# Top.net
KiCad netlist of a schematic drawn in EAGLE
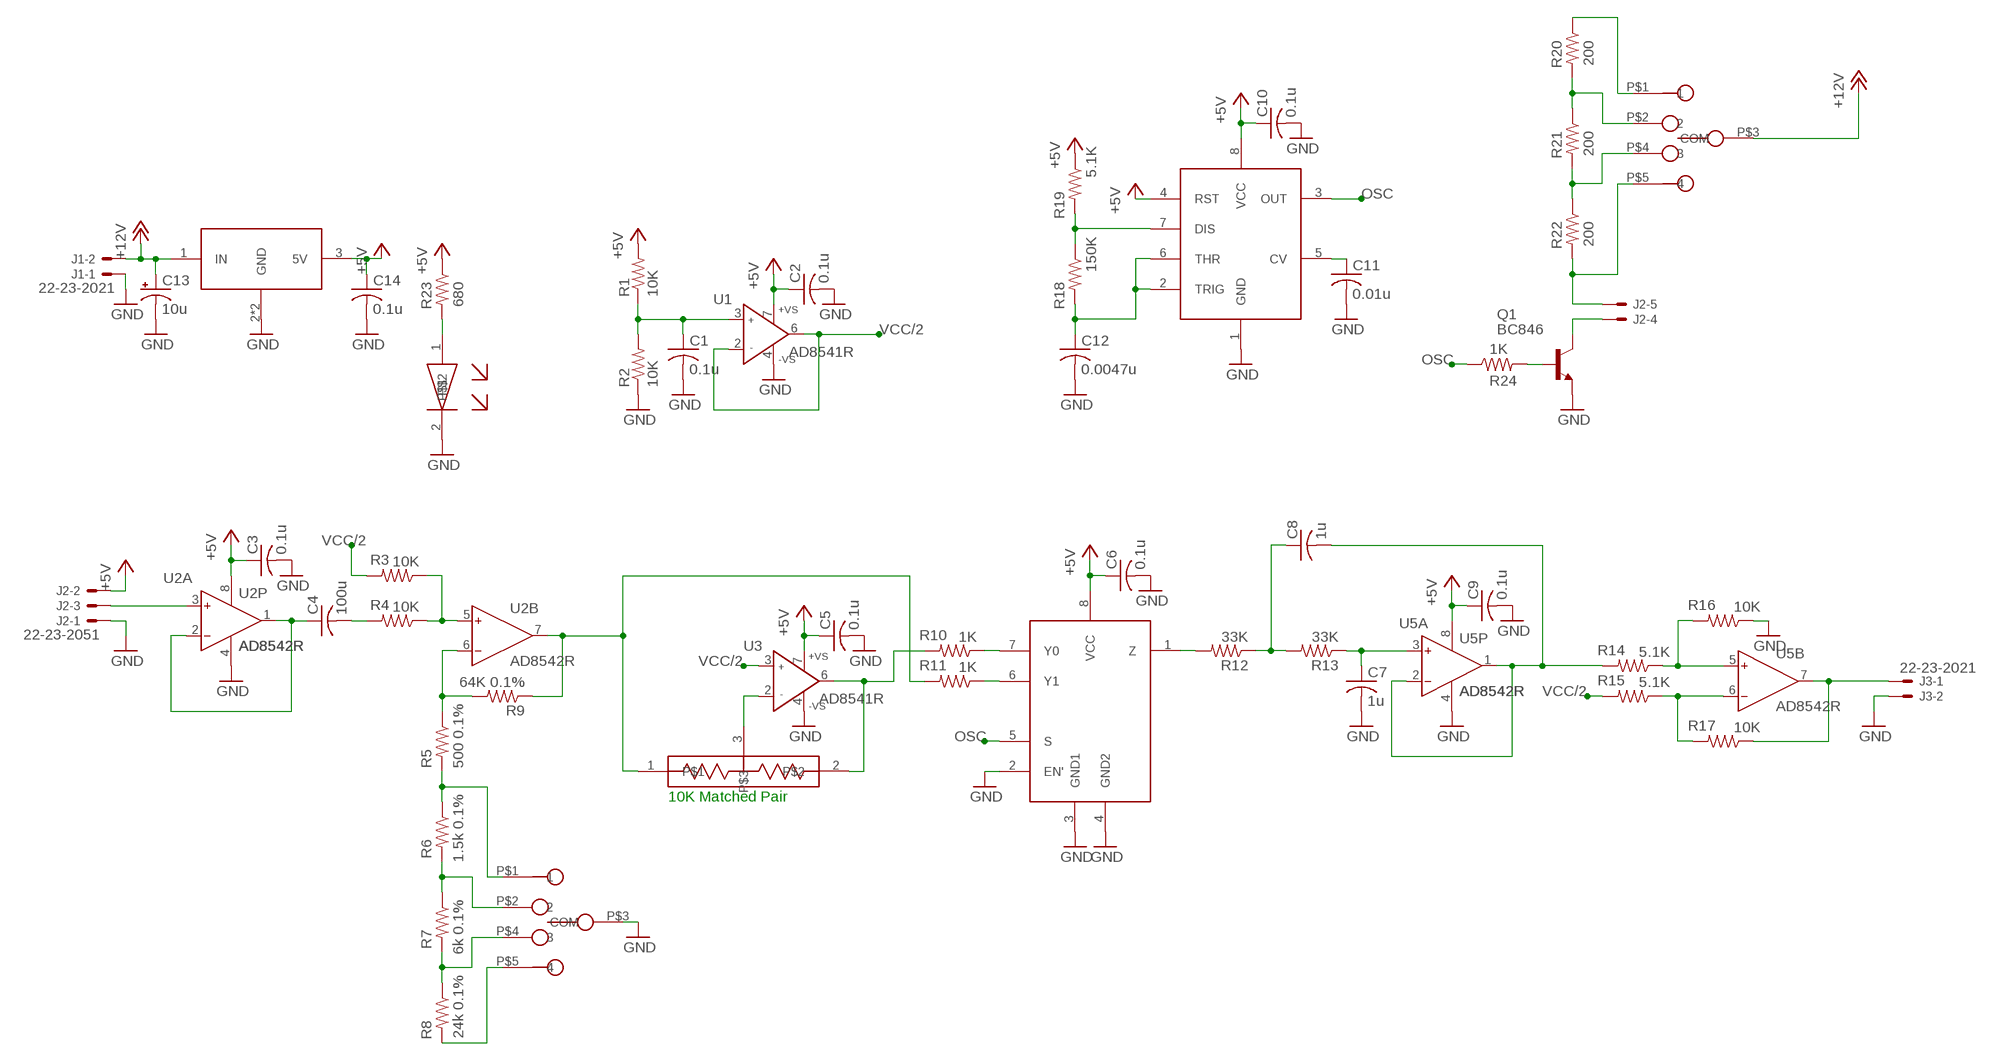
[diagram p0: schematic, sheet 1]

(export (version "E")
  (design (tool "Eeschema 10.0.6"))
  (components
    (comp (ref "C1")
      (value "0.1u")
      (footprint "eagle-import:C0805")
      (libsource (lib "eagle-import") (part "C-USC0805"))
    )
    (comp (ref "C2")
      (value "0.1u")
      (footprint "eagle-import:C0805")
      (libsource (lib "eagle-import") (part "C-USC0805"))
    )
    (comp (ref "C3")
      (value "0.1u")
      (footprint "eagle-import:C0805")
      (libsource (lib "eagle-import") (part "C-USC0805"))
    )
    (comp (ref "C4")
      (value "100u")
      (footprint "eagle-import:C1206")
      (libsource (lib "eagle-import") (part "C-USC1206"))
    )
    (comp (ref "C5")
      (value "0.1u")
      (footprint "eagle-import:C0805")
      (libsource (lib "eagle-import") (part "C-USC0805"))
    )
    (comp (ref "C6")
      (value "0.1u")
      (footprint "eagle-import:C0805")
      (libsource (lib "eagle-import") (part "C-USC0805"))
    )
    (comp (ref "C7")
      (value "1u")
      (footprint "eagle-import:C0805")
      (libsource (lib "eagle-import") (part "C-USC0805"))
    )
    (comp (ref "C8")
      (value "1u")
      (footprint "eagle-import:C0805")
      (libsource (lib "eagle-import") (part "C-USC0805"))
    )
    (comp (ref "C9")
      (value "0.1u")
      (footprint "eagle-import:C0805")
      (libsource (lib "eagle-import") (part "C-USC0805"))
    )
    (comp (ref "C10")
      (value "0.1u")
      (footprint "eagle-import:C0805")
      (libsource (lib "eagle-import") (part "C-USC0805"))
    )
    (comp (ref "C11")
      (value "0.01u")
      (footprint "eagle-import:C0805")
      (libsource (lib "eagle-import") (part "C-USC0805"))
    )
    (comp (ref "C12")
      (value "0.0047u")
      (footprint "eagle-import:C0805")
      (libsource (lib "eagle-import") (part "C-USC0805"))
    )
    (comp (ref "C13")
      (value "10u")
      (footprint "eagle-import:E2-5")
      (libsource (lib "eagle-import") (part "CPOL-USE2-5"))
    )
    (comp (ref "C14")
      (value "0.1u")
      (footprint "eagle-import:C0805")
      (libsource (lib "eagle-import") (part "C-USC0805"))
    )
    (comp (ref "D1")
      (value "LGN971")
      (footprint "eagle-import:R1206")
      (libsource (lib "eagle-import") (part "LGN971"))
    )
    (comp (ref "J1")
      (value "22-23-2021")
      (footprint "eagle-import:22-23-2021")
      (fields (field (name "MF") "MOLEX"))
      (libsource (lib "eagle-import") (part "22-23-2021"))
    )
    (comp (ref "J2")
      (value "22-23-2051")
      (footprint "eagle-import:22-23-2051")
      (fields (field (name "MF") "MOLEX"))
      (libsource (lib "eagle-import") (part "22-23-2051"))
    )
    (comp (ref "J3")
      (value "22-23-2021")
      (footprint "eagle-import:22-23-2021")
      (fields (field (name "MF") "MOLEX"))
      (libsource (lib "eagle-import") (part "22-23-2021"))
    )
    (comp (ref "Q1")
      (value "BC846")
      (footprint "eagle-import:SOT23")
      (libsource (lib "eagle-import") (part "BC846"))
    )
    (comp (ref "R1")
      (value "10K")
      (footprint "eagle-import:R0805")
      (libsource (lib "eagle-import") (part "R-US_R0805"))
    )
    (comp (ref "R2")
      (value "10K")
      (footprint "eagle-import:R0805")
      (libsource (lib "eagle-import") (part "R-US_R0805"))
    )
    (comp (ref "R3")
      (value "10K")
      (footprint "eagle-import:R0805")
      (libsource (lib "eagle-import") (part "R-US_R0805"))
    )
    (comp (ref "R4")
      (value "10K")
      (footprint "eagle-import:R0805")
      (libsource (lib "eagle-import") (part "R-US_R0805"))
    )
    (comp (ref "R5")
      (value "500 0.1%")
      (footprint "eagle-import:R0805")
      (libsource (lib "eagle-import") (part "R-US_R0805"))
    )
    (comp (ref "R6")
      (value "1.5k 0.1%")
      (footprint "eagle-import:R0805")
      (libsource (lib "eagle-import") (part "R-US_R0805"))
    )
    (comp (ref "R7")
      (value "6k 0.1%")
      (footprint "eagle-import:R0805")
      (libsource (lib "eagle-import") (part "R-US_R0805"))
    )
    (comp (ref "R8")
      (value "24k 0.1%")
      (footprint "eagle-import:R0805")
      (libsource (lib "eagle-import") (part "R-US_R0805"))
    )
    (comp (ref "R9")
      (value "64K 0.1%")
      (footprint "eagle-import:R0805")
      (libsource (lib "eagle-import") (part "R-US_R0805"))
    )
    (comp (ref "R10")
      (value "1K")
      (footprint "eagle-import:R0805")
      (libsource (lib "eagle-import") (part "R-US_R0805"))
    )
    (comp (ref "R11")
      (value "1K")
      (footprint "eagle-import:R0805")
      (libsource (lib "eagle-import") (part "R-US_R0805"))
    )
    (comp (ref "R12")
      (value "33K")
      (footprint "eagle-import:R0805")
      (libsource (lib "eagle-import") (part "R-US_R0805"))
    )
    (comp (ref "R13")
      (value "33K")
      (footprint "eagle-import:R0805")
      (libsource (lib "eagle-import") (part "R-US_R0805"))
    )
    (comp (ref "R14")
      (value "5.1K")
      (footprint "eagle-import:R0805")
      (libsource (lib "eagle-import") (part "R-US_R0805"))
    )
    (comp (ref "R15")
      (value "5.1K")
      (footprint "eagle-import:R0805")
      (libsource (lib "eagle-import") (part "R-US_R0805"))
    )
    (comp (ref "R16")
      (value "10K")
      (footprint "eagle-import:R0805")
      (libsource (lib "eagle-import") (part "R-US_R0805"))
    )
    (comp (ref "R17")
      (value "10K")
      (footprint "eagle-import:R0805")
      (libsource (lib "eagle-import") (part "R-US_R0805"))
    )
    (comp (ref "R18")
      (value "150K")
      (footprint "eagle-import:R0805")
      (libsource (lib "eagle-import") (part "R-US_R0805"))
    )
    (comp (ref "R19")
      (value "5.1K")
      (footprint "eagle-import:R0805")
      (libsource (lib "eagle-import") (part "R-US_R0805"))
    )
    (comp (ref "R20")
      (value "200")
      (footprint "eagle-import:R0805")
      (libsource (lib "eagle-import") (part "R-US_R0805"))
    )
    (comp (ref "R21")
      (value "200")
      (footprint "eagle-import:R0805")
      (libsource (lib "eagle-import") (part "R-US_R0805"))
    )
    (comp (ref "R22")
      (value "200")
      (footprint "eagle-import:R0805")
      (libsource (lib "eagle-import") (part "R-US_R0805"))
    )
    (comp (ref "R23")
      (value "680")
      (footprint "eagle-import:R0805")
      (libsource (lib "eagle-import") (part "R-US_R0805"))
    )
    (comp (ref "R24")
      (value "1K")
      (footprint "eagle-import:R0805")
      (libsource (lib "eagle-import") (part "R-US_R0805"))
    )
    (comp (ref "RN1")
      (value "MPMT2002")
      (footprint "eagle-import:SOT23")
      (libsource (lib "eagle-import") (part "MPMT2002"))
    )
    (comp (ref "SW1")
      (value "STS1400")
      (footprint "eagle-import:2-3SW")
      (libsource (lib "eagle-import") (part "STS1400"))
    )
    (comp (ref "SW2")
      (value "STS1400")
      (footprint "eagle-import:2-3SW")
      (libsource (lib "eagle-import") (part "STS1400"))
    )
    (comp (ref "U1")
      (value "AD8541R")
      (footprint "eagle-import:SO8")
      (fields (field (name "MPN") "AD8541ARZ"))
      (libsource (lib "eagle-import") (part "AD8541R"))
    )
    (comp (ref "U2")
      (value "AD8542R")
      (footprint "eagle-import:SO8")
      (fields (field (name "MF") "ALTERA CORPORATION") (field (name "MPN") "AD8542ARZ-REEL"))
      (libsource (lib "eagle-import") (part "AD8542R"))
    )
    (comp (ref "U3")
      (value "AD8541R")
      (footprint "eagle-import:SO8")
      (fields (field (name "MPN") "AD8541ARZ"))
      (libsource (lib "eagle-import") (part "AD8541R"))
    )
    (comp (ref "U4")
      (value "74LVC1G53")
      (footprint "eagle-import:SOP08")
      (libsource (lib "eagle-import") (part "74LVC1G53"))
    )
    (comp (ref "U5")
      (value "AD8542R")
      (footprint "eagle-import:SO8")
      (fields (field (name "MF") "ALTERA CORPORATION") (field (name "MPN") "AD8542ARZ-REEL"))
      (libsource (lib "eagle-import") (part "AD8542R"))
    )
    (comp (ref "U6")
      (value "NA555")
      (footprint "eagle-import:SO8")
      (libsource (lib "eagle-import") (part "NA555"))
    )
    (comp (ref "U7")
      (value "UA78M05CDCYR")
      (footprint "eagle-import:SOT223-W")
      (libsource (lib "eagle-import") (part "UA78M05CDCYR"))
    )
  )
  (nets
    (net (code "1") (name "+5V") (class "Default")
      (node (ref "C10") (pin "1") (pinfunction "1_1") (pintype "passive"))
      (node (ref "C14") (pin "1") (pinfunction "1_1") (pintype "passive"))
      (node (ref "C2") (pin "1") (pinfunction "1_1") (pintype "passive"))
      (node (ref "C3") (pin "1") (pinfunction "1_1") (pintype "passive"))
      (node (ref "C5") (pin "1") (pinfunction "1_1") (pintype "passive"))
      (node (ref "C6") (pin "1") (pinfunction "1_1") (pintype "passive"))
      (node (ref "C9") (pin "1") (pinfunction "1_1") (pintype "passive"))
      (node (ref "J2") (pin "2") (pinfunction "S_2") (pintype "passive"))
      (node (ref "R1") (pin "2") (pinfunction "2_2") (pintype "passive"))
      (node (ref "R19") (pin "1") (pinfunction "1_1") (pintype "passive"))
      (node (ref "R23") (pin "1") (pinfunction "1_1") (pintype "passive"))
      (node (ref "U1") (pin "7") (pinfunction "+VS_7") (pintype "input"))
      (node (ref "U2") (pin "8") (pinfunction "V+_8") (pintype "power_in"))
      (node (ref "U3") (pin "7") (pinfunction "+VS_7") (pintype "input"))
      (node (ref "U4") (pin "8") (pinfunction "VCC_8") (pintype "bidirectional"))
      (node (ref "U5") (pin "8") (pinfunction "V+_8") (pintype "power_in"))
      (node (ref "U6") (pin "4") (pinfunction "RST_4") (pintype "bidirectional"))
      (node (ref "U6") (pin "8") (pinfunction "VCC_8") (pintype "bidirectional"))
      (node (ref "U7") (pin "3") (pinfunction "5V_3") (pintype "bidirectional"))
    )
    (net (code "2") (name "+12V") (class "Default")
      (node (ref "C13") (pin "+") (pinfunction "+_+") (pintype "passive"))
      (node (ref "J1") (pin "2") (pinfunction "S_2") (pintype "passive"))
      (node (ref "SW2") (pin "P$3") (pinfunction "COM_P$3") (pintype "bidirectional"))
      (node (ref "U7") (pin "1") (pinfunction "IN_1") (pintype "bidirectional"))
    )
    (net (code "3") (name "/OSC") (class "Default")
      (node (ref "R24") (pin "1") (pinfunction "1_1") (pintype "passive"))
      (node (ref "U4") (pin "5") (pinfunction "S_5") (pintype "bidirectional"))
      (node (ref "U6") (pin "3") (pinfunction "OUT_3") (pintype "bidirectional"))
    )
    (net (code "4") (name "/VCC{slash}2") (class "Default")
      (node (ref "R15") (pin "2") (pinfunction "2_2") (pintype "passive"))
      (node (ref "R3") (pin "2") (pinfunction "2_2") (pintype "passive"))
      (node (ref "U1") (pin "2") (pinfunction "IN-_2") (pintype "input"))
      (node (ref "U1") (pin "6") (pinfunction "OUT_6") (pintype "output"))
      (node (ref "U3") (pin "3") (pinfunction "IN+_3") (pintype "input"))
    )
    (net (code "5") (name "GND") (class "Default")
      (node (ref "C1") (pin "2") (pinfunction "2_2") (pintype "passive"))
      (node (ref "C10") (pin "2") (pinfunction "2_2") (pintype "passive"))
      (node (ref "C11") (pin "2") (pinfunction "2_2") (pintype "passive"))
      (node (ref "C12") (pin "2") (pinfunction "2_2") (pintype "passive"))
      (node (ref "C13") (pin "-") (pinfunction "-_-") (pintype "passive"))
      (node (ref "C14") (pin "2") (pinfunction "2_2") (pintype "passive"))
      (node (ref "C2") (pin "2") (pinfunction "2_2") (pintype "passive"))
      (node (ref "C3") (pin "2") (pinfunction "2_2") (pintype "passive"))
      (node (ref "C5") (pin "2") (pinfunction "2_2") (pintype "passive"))
      (node (ref "C6") (pin "2") (pinfunction "2_2") (pintype "passive"))
      (node (ref "C7") (pin "2") (pinfunction "2_2") (pintype "passive"))
      (node (ref "C9") (pin "2") (pinfunction "2_2") (pintype "passive"))
      (node (ref "D1") (pin "2") (pinfunction "P$2_2") (pintype "bidirectional"))
      (node (ref "J1") (pin "1") (pinfunction "S_1") (pintype "passive"))
      (node (ref "J2") (pin "1") (pinfunction "S_1") (pintype "passive"))
      (node (ref "J3") (pin "2") (pinfunction "S_2") (pintype "passive"))
      (node (ref "Q1") (pin "2") (pinfunction "E_2") (pintype "passive"))
      (node (ref "R16") (pin "1") (pinfunction "1_1") (pintype "passive"))
      (node (ref "R2") (pin "1") (pinfunction "1_1") (pintype "passive"))
      (node (ref "SW1") (pin "P$3") (pinfunction "COM_P$3") (pintype "bidirectional"))
      (node (ref "U1") (pin "4") (pinfunction "-VS_4") (pintype "input"))
      (node (ref "U2") (pin "4") (pinfunction "V-_4") (pintype "power_in"))
      (node (ref "U3") (pin "4") (pinfunction "-VS_4") (pintype "input"))
      (node (ref "U4") (pin "2") (pinfunction "EN'_2") (pintype "bidirectional"))
      (node (ref "U4") (pin "3") (pinfunction "GND1_3") (pintype "bidirectional"))
      (node (ref "U4") (pin "4") (pinfunction "GND2_4") (pintype "bidirectional"))
      (node (ref "U5") (pin "4") (pinfunction "V-_4") (pintype "power_in"))
      (node (ref "U6") (pin "1") (pinfunction "GND_1") (pintype "bidirectional"))
      (node (ref "U7") (pin "2") (pinfunction "GND_2") (pintype "bidirectional"))
      (node (ref "U7") (pin "4") (pinfunction "GND_4") (pintype "bidirectional"))
    )
    (net (code "6") (name "Net-(C4-Pad2)") (class "Default")
      (node (ref "C4") (pin "2") (pinfunction "2_2") (pintype "passive"))
      (node (ref "R4") (pin "2") (pinfunction "2_2") (pintype "passive"))
    )
    (net (code "7") (name "Net-(C8-Pad1)") (class "Default")
      (node (ref "C8") (pin "1") (pinfunction "1_1") (pintype "passive"))
      (node (ref "R12") (pin "1") (pinfunction "1_1") (pintype "passive"))
      (node (ref "R13") (pin "2") (pinfunction "2_2") (pintype "passive"))
    )
    (net (code "8") (name "Net-(D1-P$1)") (class "Default")
      (node (ref "D1") (pin "1") (pinfunction "P$1_1") (pintype "bidirectional"))
      (node (ref "R23") (pin "2") (pinfunction "2_2") (pintype "passive"))
    )
    (net (code "9") (name "Net-(J2C-S)") (class "Default")
      (node (ref "J2") (pin "3") (pinfunction "S_3") (pintype "passive"))
      (node (ref "U2") (pin "3") (pinfunction "IN+_3") (pintype "input"))
    )
    (net (code "10") (name "Net-(J2D-S)") (class "Default")
      (node (ref "J2") (pin "4") (pinfunction "S_4") (pintype "passive"))
      (node (ref "Q1") (pin "3") (pinfunction "C_3") (pintype "passive"))
    )
    (net (code "11") (name "Net-(J2E-S)") (class "Default")
      (node (ref "J2") (pin "5") (pinfunction "S_5") (pintype "passive"))
      (node (ref "R22") (pin "2") (pinfunction "2_2") (pintype "passive"))
      (node (ref "SW2") (pin "P$5") (pinfunction "4_P$5") (pintype "bidirectional"))
    )
    (net (code "12") (name "Net-(J3A-S)") (class "Default")
      (node (ref "J3") (pin "1") (pinfunction "S_1") (pintype "passive"))
      (node (ref "R17") (pin "1") (pinfunction "1_1") (pintype "passive"))
      (node (ref "U5") (pin "7") (pinfunction "OUT_7") (pintype "output"))
    )
    (net (code "13") (name "Net-(Q1-B)") (class "Default")
      (node (ref "Q1") (pin "1") (pinfunction "B_1") (pintype "passive"))
      (node (ref "R24") (pin "2") (pinfunction "2_2") (pintype "passive"))
    )
    (net (code "14") (name "Net-(RN1-P$1)") (class "Default")
      (node (ref "R11") (pin "2") (pinfunction "2_2") (pintype "passive"))
      (node (ref "R9") (pin "1") (pinfunction "1_1") (pintype "passive"))
      (node (ref "RN1") (pin "1") (pinfunction "P$1_1") (pintype "bidirectional"))
      (node (ref "U2") (pin "7") (pinfunction "OUT_7") (pintype "output"))
    )
    (net (code "15") (name "Net-(RN1-P$2)") (class "Default")
      (node (ref "R10") (pin "2") (pinfunction "2_2") (pintype "passive"))
      (node (ref "RN1") (pin "2") (pinfunction "P$2_2") (pintype "bidirectional"))
      (node (ref "U3") (pin "6") (pinfunction "OUT_6") (pintype "output"))
    )
    (net (code "16") (name "Net-(RN1-P$3)") (class "Default")
      (node (ref "RN1") (pin "3") (pinfunction "P$3_3") (pintype "bidirectional"))
      (node (ref "U3") (pin "2") (pinfunction "IN-_2") (pintype "input"))
    )
    (net (code "17") (name "Net-(SW1-1)") (class "Default")
      (node (ref "R5") (pin "2") (pinfunction "2_2") (pintype "passive"))
      (node (ref "R6") (pin "1") (pinfunction "1_1") (pintype "passive"))
      (node (ref "SW1") (pin "P$1") (pinfunction "1_P$1") (pintype "bidirectional"))
    )
    (net (code "18") (name "Net-(SW1-2)") (class "Default")
      (node (ref "R6") (pin "2") (pinfunction "2_2") (pintype "passive"))
      (node (ref "R7") (pin "1") (pinfunction "1_1") (pintype "passive"))
      (node (ref "SW1") (pin "P$2") (pinfunction "2_P$2") (pintype "bidirectional"))
    )
    (net (code "19") (name "Net-(SW1-3)") (class "Default")
      (node (ref "R7") (pin "2") (pinfunction "2_2") (pintype "passive"))
      (node (ref "R8") (pin "1") (pinfunction "1_1") (pintype "passive"))
      (node (ref "SW1") (pin "P$4") (pinfunction "3_P$4") (pintype "bidirectional"))
    )
    (net (code "20") (name "Net-(SW1-4)") (class "Default")
      (node (ref "R8") (pin "2") (pinfunction "2_2") (pintype "passive"))
      (node (ref "SW1") (pin "P$5") (pinfunction "4_P$5") (pintype "bidirectional"))
    )
    (net (code "21") (name "Net-(SW2-1)") (class "Default")
      (node (ref "R20") (pin "1") (pinfunction "1_1") (pintype "passive"))
      (node (ref "SW2") (pin "P$1") (pinfunction "1_P$1") (pintype "bidirectional"))
    )
    (net (code "22") (name "Net-(SW2-2)") (class "Default")
      (node (ref "R20") (pin "2") (pinfunction "2_2") (pintype "passive"))
      (node (ref "R21") (pin "1") (pinfunction "1_1") (pintype "passive"))
      (node (ref "SW2") (pin "P$2") (pinfunction "2_P$2") (pintype "bidirectional"))
    )
    (net (code "23") (name "Net-(SW2-3)") (class "Default")
      (node (ref "R21") (pin "2") (pinfunction "2_2") (pintype "passive"))
      (node (ref "R22") (pin "1") (pinfunction "1_1") (pintype "passive"))
      (node (ref "SW2") (pin "P$4") (pinfunction "3_P$4") (pintype "bidirectional"))
    )
    (net (code "24") (name "Net-(U1-IN+)") (class "Default")
      (node (ref "C1") (pin "1") (pinfunction "1_1") (pintype "passive"))
      (node (ref "R1") (pin "1") (pinfunction "1_1") (pintype "passive"))
      (node (ref "R2") (pin "2") (pinfunction "2_2") (pintype "passive"))
      (node (ref "U1") (pin "3") (pinfunction "IN+_3") (pintype "input"))
    )
    (net (code "25") (name "Net-(U2A-IN-)") (class "Default")
      (node (ref "C4") (pin "1") (pinfunction "1_1") (pintype "passive"))
      (node (ref "U2") (pin "1") (pinfunction "OUT_1") (pintype "output"))
      (node (ref "U2") (pin "2") (pinfunction "IN-_2") (pintype "input"))
    )
    (net (code "26") (name "Net-(U2B-IN+)") (class "Default")
      (node (ref "R3") (pin "1") (pinfunction "1_1") (pintype "passive"))
      (node (ref "R4") (pin "1") (pinfunction "1_1") (pintype "passive"))
      (node (ref "U2") (pin "5") (pinfunction "IN+_5") (pintype "input"))
    )
    (net (code "27") (name "Net-(U2B-IN-)") (class "Default")
      (node (ref "R5") (pin "1") (pinfunction "1_1") (pintype "passive"))
      (node (ref "R9") (pin "2") (pinfunction "2_2") (pintype "passive"))
      (node (ref "U2") (pin "6") (pinfunction "IN-_6") (pintype "input"))
    )
    (net (code "28") (name "Net-(U4-Y0)") (class "Default")
      (node (ref "R10") (pin "1") (pinfunction "1_1") (pintype "passive"))
      (node (ref "U4") (pin "7") (pinfunction "Y0_7") (pintype "bidirectional"))
    )
    (net (code "29") (name "Net-(U4-Y1)") (class "Default")
      (node (ref "R11") (pin "1") (pinfunction "1_1") (pintype "passive"))
      (node (ref "U4") (pin "6") (pinfunction "Y1_6") (pintype "bidirectional"))
    )
    (net (code "30") (name "Net-(U4-Z)") (class "Default")
      (node (ref "R12") (pin "2") (pinfunction "2_2") (pintype "passive"))
      (node (ref "U4") (pin "1") (pinfunction "Z_1") (pintype "bidirectional"))
    )
    (net (code "31") (name "Net-(U5A-IN+)") (class "Default")
      (node (ref "C7") (pin "1") (pinfunction "1_1") (pintype "passive"))
      (node (ref "R13") (pin "1") (pinfunction "1_1") (pintype "passive"))
      (node (ref "U5") (pin "3") (pinfunction "IN+_3") (pintype "input"))
    )
    (net (code "32") (name "Net-(U5A-IN-)") (class "Default")
      (node (ref "C8") (pin "2") (pinfunction "2_2") (pintype "passive"))
      (node (ref "R14") (pin "2") (pinfunction "2_2") (pintype "passive"))
      (node (ref "U5") (pin "1") (pinfunction "OUT_1") (pintype "output"))
      (node (ref "U5") (pin "2") (pinfunction "IN-_2") (pintype "input"))
    )
    (net (code "33") (name "Net-(U5B-IN+)") (class "Default")
      (node (ref "R14") (pin "1") (pinfunction "1_1") (pintype "passive"))
      (node (ref "R16") (pin "2") (pinfunction "2_2") (pintype "passive"))
      (node (ref "U5") (pin "5") (pinfunction "IN+_5") (pintype "input"))
    )
    (net (code "34") (name "Net-(U5B-IN-)") (class "Default")
      (node (ref "R15") (pin "1") (pinfunction "1_1") (pintype "passive"))
      (node (ref "R17") (pin "2") (pinfunction "2_2") (pintype "passive"))
      (node (ref "U5") (pin "6") (pinfunction "IN-_6") (pintype "input"))
    )
    (net (code "35") (name "Net-(U6-CV)") (class "Default")
      (node (ref "C11") (pin "1") (pinfunction "1_1") (pintype "passive"))
      (node (ref "U6") (pin "5") (pinfunction "CV_5") (pintype "bidirectional"))
    )
    (net (code "36") (name "Net-(U6-DIS)") (class "Default")
      (node (ref "R18") (pin "1") (pinfunction "1_1") (pintype "passive"))
      (node (ref "R19") (pin "2") (pinfunction "2_2") (pintype "passive"))
      (node (ref "U6") (pin "7") (pinfunction "DIS_7") (pintype "bidirectional"))
    )
    (net (code "37") (name "Net-(U6-THR)") (class "Default")
      (node (ref "C12") (pin "1") (pinfunction "1_1") (pintype "passive"))
      (node (ref "R18") (pin "2") (pinfunction "2_2") (pintype "passive"))
      (node (ref "U6") (pin "2") (pinfunction "TRIG_2") (pintype "bidirectional"))
      (node (ref "U6") (pin "6") (pinfunction "THR_6") (pintype "bidirectional"))
    )
  )
)
